# PVScontroller.net
KiCad netlist of a schematic drawn in EAGLE
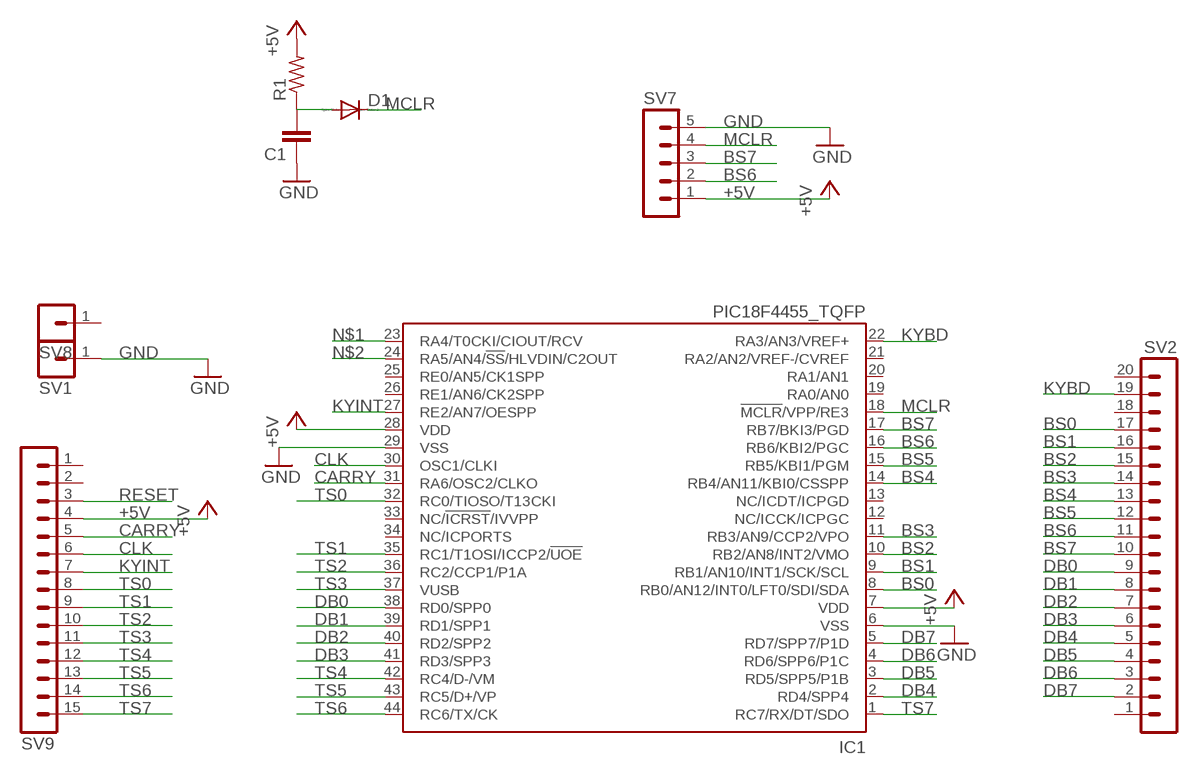
[diagram p0: schematic, sheet 1]

(export (version "E")
  (design (tool "Eeschema 10.0.6"))
  (components
    (comp (ref "C1")
      (value "C-EUC0805")
      (footprint "eagle-import:C0805")
      (libsource (lib "eagle-import") (part "C-EUC0805"))
    )
    (comp (ref "D1")
      (value "DIODE-SOD80C")
      (footprint "eagle-import:SOD80C")
      (libsource (lib "eagle-import") (part "DIODE-SOD80C"))
    )
    (comp (ref "IC1")
      (value "PIC18F4455_TQFP")
      (footprint "eagle-import:TQFP44")
      (fields (field (name "MF") "MICROCHIP") (field (name "MPN") "PIC18F4455-I/PT"))
      (libsource (lib "eagle-import") (part "PIC18F4_TQFP455"))
    )
    (comp (ref "R1")
      (value "R-US_R0805")
      (footprint "eagle-import:R0805")
      (libsource (lib "eagle-import") (part "R-US_R0805"))
    )
    (comp (ref "SV1")
      (value "MA01-1")
      (footprint "eagle-import:MA01-1")
      (libsource (lib "eagle-import") (part "MA01-1"))
    )
    (comp (ref "SV2")
      (value "MA20-1")
      (footprint "eagle-import:MA20-1")
      (libsource (lib "eagle-import") (part "MA20-1"))
    )
    (comp (ref "SV7")
      (value "MA05-1")
      (footprint "eagle-import:MA05-1")
      (libsource (lib "eagle-import") (part "MA05-1"))
    )
    (comp (ref "SV8")
      (value "MA01-1")
      (footprint "eagle-import:MA01-1")
      (libsource (lib "eagle-import") (part "MA01-1"))
    )
    (comp (ref "SV9")
      (value "MA15-1")
      (footprint "eagle-import:MA15-1")
      (libsource (lib "eagle-import") (part "MA15-1"))
    )
  )
  (nets
    (net (code "1") (name "+5V") (class "Default")
      (node (ref "IC1") (pin "28") (pinfunction "VDD_28") (pintype "power_in"))
      (node (ref "IC1") (pin "7") (pinfunction "VDD_7") (pintype "power_in"))
      (node (ref "R1") (pin "2") (pinfunction "2_2") (pintype "passive"))
      (node (ref "SV7") (pin "1") (pinfunction "1_1") (pintype "passive"))
      (node (ref "SV9") (pin "4") (pinfunction "4_4") (pintype "passive"))
    )
    (net (code "2") (name "/BS0") (class "Default")
      (node (ref "IC1") (pin "8") (pinfunction "RB0/AN12/INT0/LFT0/SDI/SDA_8") (pintype "bidirectional"))
      (node (ref "SV2") (pin "17") (pinfunction "17_17") (pintype "passive"))
    )
    (net (code "3") (name "/BS1") (class "Default")
      (node (ref "IC1") (pin "9") (pinfunction "RB1/AN10/INT1/SCK/SCL_9") (pintype "bidirectional"))
      (node (ref "SV2") (pin "16") (pinfunction "16_16") (pintype "passive"))
    )
    (net (code "4") (name "/BS2") (class "Default")
      (node (ref "IC1") (pin "10") (pinfunction "RB2/AN8/INT2/VMO_10") (pintype "bidirectional"))
      (node (ref "SV2") (pin "15") (pinfunction "15_15") (pintype "passive"))
    )
    (net (code "5") (name "/BS3") (class "Default")
      (node (ref "IC1") (pin "11") (pinfunction "RB3/AN9/CCP2/VPO_11") (pintype "bidirectional"))
      (node (ref "SV2") (pin "14") (pinfunction "14_14") (pintype "passive"))
    )
    (net (code "6") (name "/BS4") (class "Default")
      (node (ref "IC1") (pin "14") (pinfunction "RB4/AN11/KBI0/CSSPP_14") (pintype "bidirectional"))
      (node (ref "SV2") (pin "13") (pinfunction "13_13") (pintype "passive"))
    )
    (net (code "7") (name "/BS5") (class "Default")
      (node (ref "IC1") (pin "15") (pinfunction "RB5/KBI1/PGM_15") (pintype "bidirectional"))
      (node (ref "SV2") (pin "12") (pinfunction "12_12") (pintype "passive"))
    )
    (net (code "8") (name "/BS6") (class "Default")
      (node (ref "IC1") (pin "16") (pinfunction "RB6/KBI2/PGC_16") (pintype "bidirectional"))
      (node (ref "SV2") (pin "11") (pinfunction "11_11") (pintype "passive"))
      (node (ref "SV7") (pin "2") (pinfunction "2_2") (pintype "passive"))
    )
    (net (code "9") (name "/BS7") (class "Default")
      (node (ref "IC1") (pin "17") (pinfunction "RB7/BKI3/PGD_17") (pintype "bidirectional"))
      (node (ref "SV2") (pin "10") (pinfunction "10_10") (pintype "passive"))
      (node (ref "SV7") (pin "3") (pinfunction "3_3") (pintype "passive"))
    )
    (net (code "10") (name "/CARRY") (class "Default")
      (node (ref "IC1") (pin "31") (pinfunction "RA6/OSC2/CLKO_31") (pintype "output"))
      (node (ref "SV9") (pin "5") (pinfunction "5_5") (pintype "passive"))
    )
    (net (code "11") (name "/CLK") (class "Default")
      (node (ref "IC1") (pin "30") (pinfunction "OSC1/CLKI_30") (pintype "input"))
      (node (ref "SV9") (pin "6") (pinfunction "6_6") (pintype "passive"))
    )
    (net (code "12") (name "/DB0") (class "Default")
      (node (ref "IC1") (pin "38") (pinfunction "RD0/SPP0_38") (pintype "bidirectional"))
      (node (ref "SV2") (pin "9") (pinfunction "9_9") (pintype "passive"))
    )
    (net (code "13") (name "/DB1") (class "Default")
      (node (ref "IC1") (pin "39") (pinfunction "RD1/SPP1_39") (pintype "bidirectional"))
      (node (ref "SV2") (pin "8") (pinfunction "8_8") (pintype "passive"))
    )
    (net (code "14") (name "/DB2") (class "Default")
      (node (ref "IC1") (pin "40") (pinfunction "RD2/SPP2_40") (pintype "bidirectional"))
      (node (ref "SV2") (pin "7") (pinfunction "7_7") (pintype "passive"))
    )
    (net (code "15") (name "/DB3") (class "Default")
      (node (ref "IC1") (pin "41") (pinfunction "RD3/SPP3_41") (pintype "bidirectional"))
      (node (ref "SV2") (pin "6") (pinfunction "6_6") (pintype "passive"))
    )
    (net (code "16") (name "/DB4") (class "Default")
      (node (ref "IC1") (pin "2") (pinfunction "RD4/SPP4_2") (pintype "bidirectional"))
      (node (ref "SV2") (pin "5") (pinfunction "5_5") (pintype "passive"))
    )
    (net (code "17") (name "/DB5") (class "Default")
      (node (ref "IC1") (pin "3") (pinfunction "RD5/SPP5/P1B_3") (pintype "bidirectional"))
      (node (ref "SV2") (pin "4") (pinfunction "4_4") (pintype "passive"))
    )
    (net (code "18") (name "/DB6") (class "Default")
      (node (ref "IC1") (pin "4") (pinfunction "RD6/SPP6/P1C_4") (pintype "bidirectional"))
      (node (ref "SV2") (pin "3") (pinfunction "3_3") (pintype "passive"))
    )
    (net (code "19") (name "/DB7") (class "Default")
      (node (ref "IC1") (pin "5") (pinfunction "RD7/SPP7/P1D_5") (pintype "bidirectional"))
      (node (ref "SV2") (pin "2") (pinfunction "2_2") (pintype "passive"))
    )
    (net (code "20") (name "/KYBD") (class "Default")
      (node (ref "IC1") (pin "22") (pinfunction "RA3/AN3/VREF+_22") (pintype "bidirectional"))
      (node (ref "SV2") (pin "19") (pinfunction "19_19") (pintype "passive"))
    )
    (net (code "21") (name "/KYINT") (class "Default")
      (node (ref "IC1") (pin "27") (pinfunction "RE2/AN7/OESPP_27") (pintype "bidirectional"))
      (node (ref "SV9") (pin "7") (pinfunction "7_7") (pintype "passive"))
    )
    (net (code "22") (name "/MCLR") (class "Default")
      (node (ref "D1") (pin "C") (pinfunction "C_C") (pintype "passive"))
      (node (ref "IC1") (pin "18") (pinfunction "~{MCLR}/VPP/RE3_18") (pintype "input"))
      (node (ref "SV7") (pin "4") (pinfunction "4_4") (pintype "passive"))
    )
    (net (code "23") (name "/N$1") (class "Default")
      (node (ref "IC1") (pin "23") (pinfunction "RA4/T0CKI/CIOUT/RCV_23") (pintype "bidirectional"))
    )
    (net (code "24") (name "/N$2") (class "Default")
      (node (ref "IC1") (pin "24") (pinfunction "RA5/AN4/~{SS}/HLVDIN/C2OUT_24") (pintype "bidirectional"))
    )
    (net (code "25") (name "/RESET") (class "Default")
      (node (ref "SV9") (pin "3") (pinfunction "3_3") (pintype "passive"))
    )
    (net (code "26") (name "/TS0") (class "Default")
      (node (ref "IC1") (pin "32") (pinfunction "RC0/TIOSO/T13CKI_32") (pintype "bidirectional"))
      (node (ref "SV9") (pin "8") (pinfunction "8_8") (pintype "passive"))
    )
    (net (code "27") (name "/TS1") (class "Default")
      (node (ref "IC1") (pin "35") (pinfunction "RC1/T1OSI/ICCP2/~{UOE}_35") (pintype "bidirectional"))
      (node (ref "SV9") (pin "9") (pinfunction "9_9") (pintype "passive"))
    )
    (net (code "28") (name "/TS2") (class "Default")
      (node (ref "IC1") (pin "36") (pinfunction "RC2/CCP1/P1A_36") (pintype "bidirectional"))
      (node (ref "SV9") (pin "10") (pinfunction "10_10") (pintype "passive"))
    )
    (net (code "29") (name "/TS3") (class "Default")
      (node (ref "IC1") (pin "37") (pinfunction "VUSB_37") (pintype "bidirectional"))
      (node (ref "SV9") (pin "11") (pinfunction "11_11") (pintype "passive"))
    )
    (net (code "30") (name "/TS4") (class "Default")
      (node (ref "IC1") (pin "42") (pinfunction "RC4/D-/VM_42") (pintype "bidirectional"))
      (node (ref "SV9") (pin "12") (pinfunction "12_12") (pintype "passive"))
    )
    (net (code "31") (name "/TS5") (class "Default")
      (node (ref "IC1") (pin "43") (pinfunction "RC5/D+/VP_43") (pintype "bidirectional"))
      (node (ref "SV9") (pin "13") (pinfunction "13_13") (pintype "passive"))
    )
    (net (code "32") (name "/TS6") (class "Default")
      (node (ref "IC1") (pin "44") (pinfunction "RC6/TX/CK_44") (pintype "bidirectional"))
      (node (ref "SV9") (pin "14") (pinfunction "14_14") (pintype "passive"))
    )
    (net (code "33") (name "/TS7") (class "Default")
      (node (ref "IC1") (pin "1") (pinfunction "RC7/RX/DT/SDO_1") (pintype "bidirectional"))
      (node (ref "SV9") (pin "15") (pinfunction "15_15") (pintype "passive"))
    )
    (net (code "34") (name "GND") (class "Default")
      (node (ref "C1") (pin "1") (pinfunction "1_1") (pintype "passive"))
      (node (ref "IC1") (pin "29") (pinfunction "VSS_29") (pintype "power_in"))
      (node (ref "IC1") (pin "6") (pinfunction "VSS_6") (pintype "power_in"))
      (node (ref "SV1") (pin "1") (pinfunction "1_1") (pintype "passive"))
      (node (ref "SV7") (pin "5") (pinfunction "5_5") (pintype "passive"))
    )
    (net (code "35") (name "Net-(C1-Pad2)") (class "Default")
      (node (ref "C1") (pin "2") (pinfunction "2_2") (pintype "passive"))
      (node (ref "D1") (pin "A") (pinfunction "A_A") (pintype "passive"))
      (node (ref "R1") (pin "1") (pinfunction "1_1") (pintype "passive"))
    )
    (net (code "36") (name "unconnected-(IC1-NC{slash}ICCK{slash}ICPGC-Pad12)") (class "Default")
      (node (ref "IC1") (pin "12") (pinfunction "NC/ICCK/ICPGC_12") (pintype "bidirectional"))
    )
    (net (code "37") (name "unconnected-(IC1-NC{slash}ICDT{slash}ICPGD-Pad13)") (class "Default")
      (node (ref "IC1") (pin "13") (pinfunction "NC/ICDT/ICPGD_13") (pintype "bidirectional"))
    )
    (net (code "38") (name "unconnected-(IC1-NC{slash}ICPORTS-Pad34)") (class "Default")
      (node (ref "IC1") (pin "34") (pinfunction "NC/ICPORTS_34") (pintype "input"))
    )
    (net (code "39") (name "unconnected-(IC1-NC{slash}~{ICRST}{slash}IVVPP-Pad33)") (class "Default")
      (node (ref "IC1") (pin "33") (pinfunction "NC/~{ICRST}/IVVPP_33") (pintype "input"))
    )
    (net (code "40") (name "unconnected-(IC1-RA0{slash}AN0-Pad19)") (class "Default")
      (node (ref "IC1") (pin "19") (pinfunction "RA0/AN0_19") (pintype "bidirectional"))
    )
    (net (code "41") (name "unconnected-(IC1-RA1{slash}AN1-Pad20)") (class "Default")
      (node (ref "IC1") (pin "20") (pinfunction "RA1/AN1_20") (pintype "bidirectional"))
    )
    (net (code "42") (name "unconnected-(IC1-RA2{slash}AN2{slash}VREF-{slash}CVREF-Pad21)") (class "Default")
      (node (ref "IC1") (pin "21") (pinfunction "RA2/AN2/VREF-/CVREF_21") (pintype "bidirectional"))
    )
    (net (code "43") (name "unconnected-(IC1-RE0{slash}AN5{slash}CK1SPP-Pad25)") (class "Default")
      (node (ref "IC1") (pin "25") (pinfunction "RE0/AN5/CK1SPP_25") (pintype "bidirectional"))
    )
    (net (code "44") (name "unconnected-(IC1-RE1{slash}AN6{slash}CK2SPP-Pad26)") (class "Default")
      (node (ref "IC1") (pin "26") (pinfunction "RE1/AN6/CK2SPP_26") (pintype "bidirectional"))
    )
    (net (code "45") (name "unconnected-(SV2-Pad1)") (class "Default")
      (node (ref "SV2") (pin "1") (pinfunction "1_1") (pintype "passive"))
    )
    (net (code "46") (name "unconnected-(SV2-Pad18)") (class "Default")
      (node (ref "SV2") (pin "18") (pinfunction "18_18") (pintype "passive"))
    )
    (net (code "47") (name "unconnected-(SV2-Pad20)") (class "Default")
      (node (ref "SV2") (pin "20") (pinfunction "20_20") (pintype "passive"))
    )
    (net (code "48") (name "unconnected-(SV8-Pad1)") (class "Default")
      (node (ref "SV8") (pin "1") (pinfunction "1_1") (pintype "passive"))
    )
    (net (code "49") (name "unconnected-(SV9-Pad1)") (class "Default")
      (node (ref "SV9") (pin "1") (pinfunction "1_1") (pintype "passive"))
    )
    (net (code "50") (name "unconnected-(SV9-Pad2)") (class "Default")
      (node (ref "SV9") (pin "2") (pinfunction "2_2") (pintype "passive"))
    )
  )
)
